# pcb.net
KiCad netlist of a schematic drawn in EasyEDA Pro
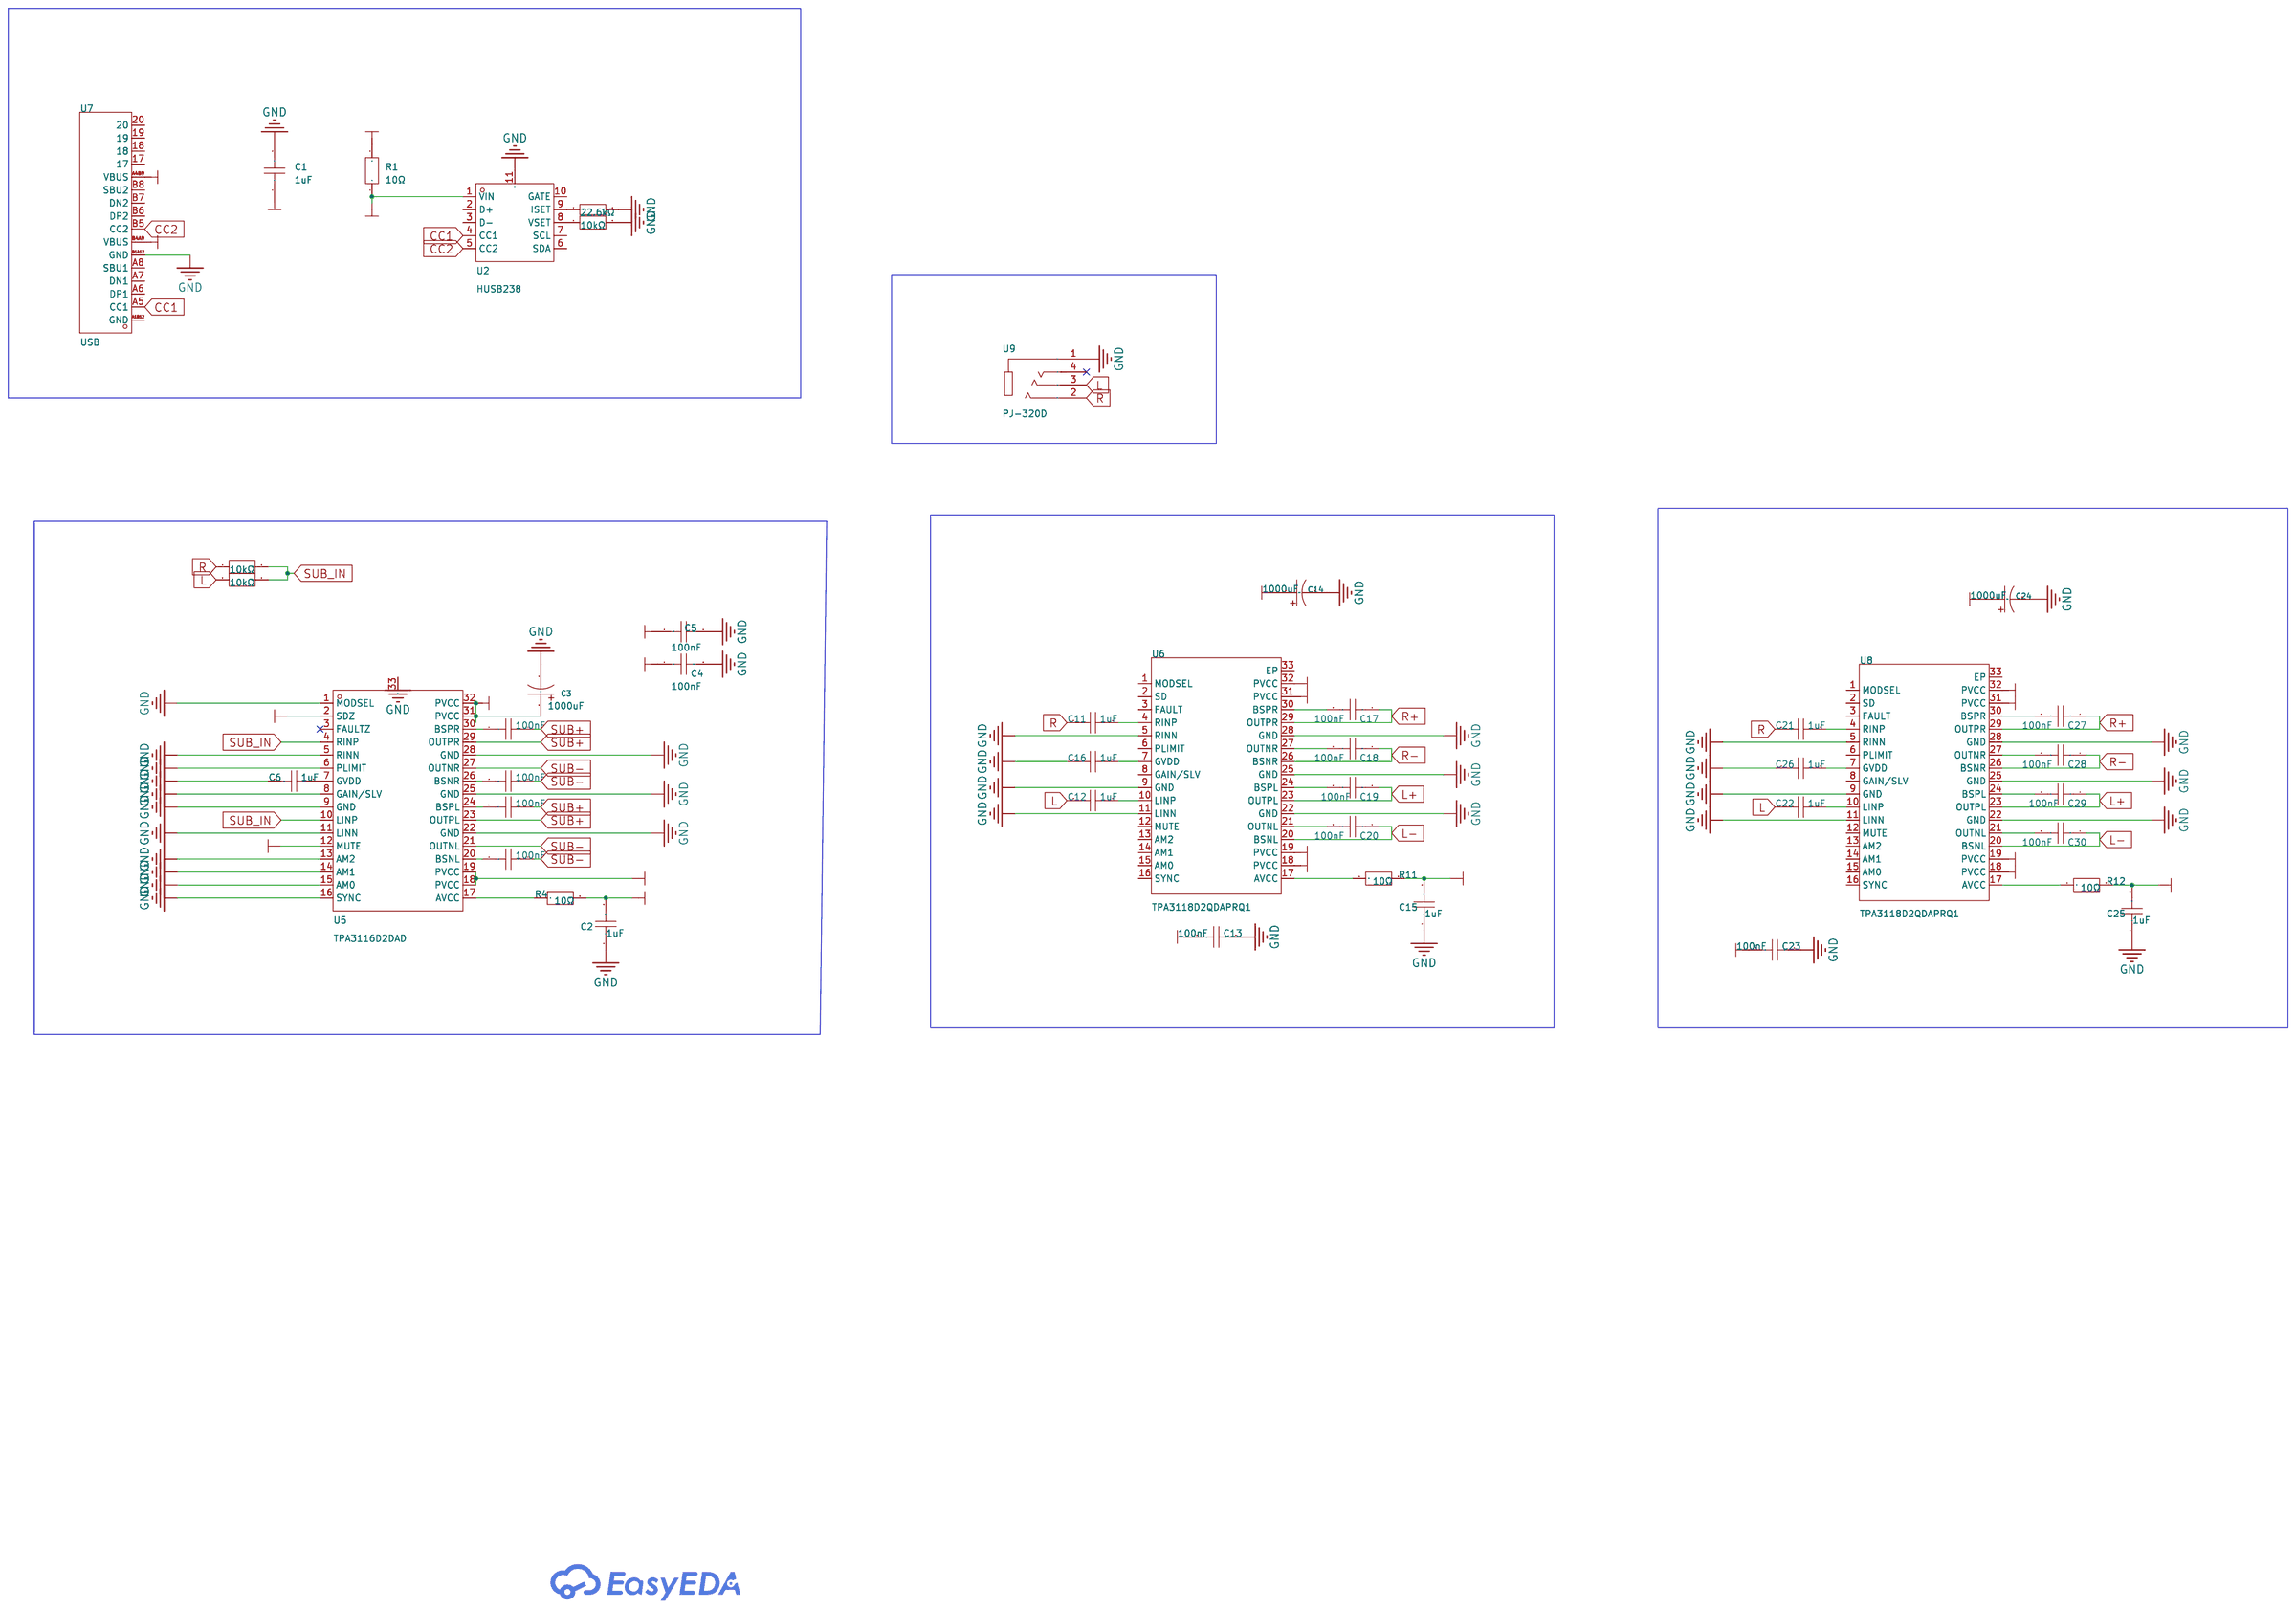
[diagram p0: schematic sheet]

(export (version "E")
  (design (tool "Eeschema 10.0.6"))
  (components
    (comp (ref "C1")
      (value "1uF")
      (footprint "easyedapro:C0805")
      (fields
        (field (name "Manufacturer Part") "LMK212BJ105KG-T")
        (field (name "Manufacturer") "TAIYO YUDEN(太诱)")
      )
      (libsource (lib "easyedapro") (part "LMK212BJ105KG-T"))
    )
    (comp (ref "C2")
      (value "1uF")
      (footprint "easyedapro:C0805")
      (fields
        (field (name "Manufacturer Part") "LMK212BJ105KG-T")
        (field (name "Manufacturer") "TAIYO YUDEN(太诱)")
      )
      (libsource (lib "easyedapro") (part "LMK212BJ105KG-T"))
    )
    (comp (ref "C3")
      (value "1000uF")
      (footprint "easyedapro:CAP-TH_BD12.5-P5.00-D0.6-FD")
      (fields
        (field (name "Manufacturer Part") "ECR1HBK102MLL125025")
        (field (name "Manufacturer") "Jianghai(南通江海)")
      )
      (libsource (lib "easyedapro") (part "ECR1HBK102MLL125025"))
    )
    (comp (ref "C4")
      (value "100nF")
      (footprint "easyedapro:C0603")
      (description "Capacitance:100nF Tolerance:±10% Tolerance:±10% Voltage Rating:50V Temperature Coefficient:X7R")
      (fields
        (field (name "Manufacturer Part") "CC0603KRX7R9BB104")
        (field (name "Manufacturer") "YAGEO(国巨)")
      )
      (libsource (lib "easyedapro") (part "CC0603KRX7R9BB104"))
    )
    (comp (ref "C5")
      (value "100nF")
      (footprint "easyedapro:C0603")
      (description "Capacitance:100nF Tolerance:±10% Tolerance:±10% Voltage Rating:50V Temperature Coefficient:X7R")
      (fields
        (field (name "Manufacturer Part") "CC0603KRX7R9BB104")
        (field (name "Manufacturer") "YAGEO(国巨)")
      )
      (libsource (lib "easyedapro") (part "CC0603KRX7R9BB104"))
    )
    (comp (ref "C6")
      (value "1uF")
      (footprint "easyedapro:C0805")
      (fields
        (field (name "Manufacturer Part") "LMK212BJ105KG-T")
        (field (name "Manufacturer") "TAIYO YUDEN(太诱)")
      )
      (libsource (lib "easyedapro") (part "LMK212BJ105KG-T"))
    )
    (comp (ref "C7")
      (value "100nF")
      (footprint "easyedapro:C0603")
      (description "Capacitance:100nF Tolerance:±10% Tolerance:±10% Voltage Rating:50V Temperature Coefficient:X7R")
      (fields
        (field (name "Manufacturer Part") "CC0603KRX7R9BB104")
        (field (name "Manufacturer") "YAGEO(国巨)")
      )
      (libsource (lib "easyedapro") (part "CC0603KRX7R9BB104"))
    )
    (comp (ref "C8")
      (value "100nF")
      (footprint "easyedapro:C0603")
      (description "Capacitance:100nF Tolerance:±10% Tolerance:±10% Voltage Rating:50V Temperature Coefficient:X7R")
      (fields
        (field (name "Manufacturer Part") "CC0603KRX7R9BB104")
        (field (name "Manufacturer") "YAGEO(国巨)")
      )
      (libsource (lib "easyedapro") (part "CC0603KRX7R9BB104"))
    )
    (comp (ref "C9")
      (value "100nF")
      (footprint "easyedapro:C0603")
      (description "Capacitance:100nF Tolerance:±10% Tolerance:±10% Voltage Rating:50V Temperature Coefficient:X7R")
      (fields
        (field (name "Manufacturer Part") "CC0603KRX7R9BB104")
        (field (name "Manufacturer") "YAGEO(国巨)")
      )
      (libsource (lib "easyedapro") (part "CC0603KRX7R9BB104"))
    )
    (comp (ref "C10")
      (value "100nF")
      (footprint "easyedapro:C0603")
      (description "Capacitance:100nF Tolerance:±10% Tolerance:±10% Voltage Rating:50V Temperature Coefficient:X7R")
      (fields
        (field (name "Manufacturer Part") "CC0603KRX7R9BB104")
        (field (name "Manufacturer") "YAGEO(国巨)")
      )
      (libsource (lib "easyedapro") (part "CC0603KRX7R9BB104"))
    )
    (comp (ref "C11")
      (value "1uF")
      (footprint "easyedapro:C0805")
      (fields
        (field (name "Manufacturer Part") "LMK212BJ105KG-T")
        (field (name "Manufacturer") "TAIYO YUDEN(太诱)")
      )
      (libsource (lib "easyedapro") (part "LMK212BJ105KG-T"))
    )
    (comp (ref "C12")
      (value "1uF")
      (footprint "easyedapro:C0805")
      (fields
        (field (name "Manufacturer Part") "LMK212BJ105KG-T")
        (field (name "Manufacturer") "TAIYO YUDEN(太诱)")
      )
      (libsource (lib "easyedapro") (part "LMK212BJ105KG-T"))
    )
    (comp (ref "C13")
      (value "100nF")
      (footprint "easyedapro:C0603")
      (description "Capacitance:100nF Tolerance:±10% Tolerance:±10% Voltage Rating:50V Temperature Coefficient:X7R")
      (fields
        (field (name "Manufacturer Part") "CC0603KRX7R9BB104")
        (field (name "Manufacturer") "YAGEO(国巨)")
      )
      (libsource (lib "easyedapro") (part "CC0603KRX7R9BB104"))
    )
    (comp (ref "C14")
      (value "1000uF")
      (footprint "easyedapro:CAP-TH_BD12.5-P5.00-D0.6-FD")
      (fields
        (field (name "Manufacturer Part") "ECR1HBK102MLL125025")
        (field (name "Manufacturer") "Jianghai(南通江海)")
      )
      (libsource (lib "easyedapro") (part "ECR1HBK102MLL125025"))
    )
    (comp (ref "C15")
      (value "1uF")
      (footprint "easyedapro:C0805")
      (fields
        (field (name "Manufacturer Part") "LMK212BJ105KG-T")
        (field (name "Manufacturer") "TAIYO YUDEN(太诱)")
      )
      (libsource (lib "easyedapro") (part "LMK212BJ105KG-T"))
    )
    (comp (ref "C16")
      (value "1uF")
      (footprint "easyedapro:C0805")
      (fields
        (field (name "Manufacturer Part") "LMK212BJ105KG-T")
        (field (name "Manufacturer") "TAIYO YUDEN(太诱)")
      )
      (libsource (lib "easyedapro") (part "LMK212BJ105KG-T"))
    )
    (comp (ref "C17")
      (value "100nF")
      (footprint "easyedapro:C0603")
      (description "Capacitance:100nF Tolerance:±10% Tolerance:±10% Voltage Rating:50V Temperature Coefficient:X7R")
      (fields
        (field (name "Manufacturer Part") "CC0603KRX7R9BB104")
        (field (name "Manufacturer") "YAGEO(国巨)")
      )
      (libsource (lib "easyedapro") (part "CC0603KRX7R9BB104"))
    )
    (comp (ref "C18")
      (value "100nF")
      (footprint "easyedapro:C0603")
      (description "Capacitance:100nF Tolerance:±10% Tolerance:±10% Voltage Rating:50V Temperature Coefficient:X7R")
      (fields
        (field (name "Manufacturer Part") "CC0603KRX7R9BB104")
        (field (name "Manufacturer") "YAGEO(国巨)")
      )
      (libsource (lib "easyedapro") (part "CC0603KRX7R9BB104"))
    )
    (comp (ref "C19")
      (value "100nF")
      (footprint "easyedapro:C0603")
      (description "Capacitance:100nF Tolerance:±10% Tolerance:±10% Voltage Rating:50V Temperature Coefficient:X7R")
      (fields
        (field (name "Manufacturer Part") "CC0603KRX7R9BB104")
        (field (name "Manufacturer") "YAGEO(国巨)")
      )
      (libsource (lib "easyedapro") (part "CC0603KRX7R9BB104"))
    )
    (comp (ref "C20")
      (value "100nF")
      (footprint "easyedapro:C0603")
      (description "Capacitance:100nF Tolerance:±10% Tolerance:±10% Voltage Rating:50V Temperature Coefficient:X7R")
      (fields
        (field (name "Manufacturer Part") "CC0603KRX7R9BB104")
        (field (name "Manufacturer") "YAGEO(国巨)")
      )
      (libsource (lib "easyedapro") (part "CC0603KRX7R9BB104"))
    )
    (comp (ref "C21")
      (value "1uF")
      (footprint "easyedapro:C0805")
      (fields
        (field (name "Manufacturer Part") "LMK212BJ105KG-T")
        (field (name "Manufacturer") "TAIYO YUDEN(太诱)")
      )
      (libsource (lib "easyedapro") (part "LMK212BJ105KG-T"))
    )
    (comp (ref "C22")
      (value "1uF")
      (footprint "easyedapro:C0805")
      (fields
        (field (name "Manufacturer Part") "LMK212BJ105KG-T")
        (field (name "Manufacturer") "TAIYO YUDEN(太诱)")
      )
      (libsource (lib "easyedapro") (part "LMK212BJ105KG-T"))
    )
    (comp (ref "C23")
      (value "100nF")
      (footprint "easyedapro:C0603")
      (description "Capacitance:100nF Tolerance:±10% Tolerance:±10% Voltage Rating:50V Temperature Coefficient:X7R")
      (fields
        (field (name "Manufacturer Part") "CC0603KRX7R9BB104")
        (field (name "Manufacturer") "YAGEO(国巨)")
      )
      (libsource (lib "easyedapro") (part "CC0603KRX7R9BB104"))
    )
    (comp (ref "C24")
      (value "1000uF")
      (footprint "easyedapro:CAP-TH_BD12.5-P5.00-D0.6-FD")
      (fields
        (field (name "Manufacturer Part") "ECR1HBK102MLL125025")
        (field (name "Manufacturer") "Jianghai(南通江海)")
      )
      (libsource (lib "easyedapro") (part "ECR1HBK102MLL125025"))
    )
    (comp (ref "C25")
      (value "1uF")
      (footprint "easyedapro:C0805")
      (fields
        (field (name "Manufacturer Part") "LMK212BJ105KG-T")
        (field (name "Manufacturer") "TAIYO YUDEN(太诱)")
      )
      (libsource (lib "easyedapro") (part "LMK212BJ105KG-T"))
    )
    (comp (ref "C26")
      (value "1uF")
      (footprint "easyedapro:C0805")
      (fields
        (field (name "Manufacturer Part") "LMK212BJ105KG-T")
        (field (name "Manufacturer") "TAIYO YUDEN(太诱)")
      )
      (libsource (lib "easyedapro") (part "LMK212BJ105KG-T"))
    )
    (comp (ref "C27")
      (value "100nF")
      (footprint "easyedapro:C0603")
      (description "Capacitance:100nF Tolerance:±10% Tolerance:±10% Voltage Rating:50V Temperature Coefficient:X7R")
      (fields
        (field (name "Manufacturer Part") "CC0603KRX7R9BB104")
        (field (name "Manufacturer") "YAGEO(国巨)")
      )
      (libsource (lib "easyedapro") (part "CC0603KRX7R9BB104"))
    )
    (comp (ref "C28")
      (value "100nF")
      (footprint "easyedapro:C0603")
      (description "Capacitance:100nF Tolerance:±10% Tolerance:±10% Voltage Rating:50V Temperature Coefficient:X7R")
      (fields
        (field (name "Manufacturer Part") "CC0603KRX7R9BB104")
        (field (name "Manufacturer") "YAGEO(国巨)")
      )
      (libsource (lib "easyedapro") (part "CC0603KRX7R9BB104"))
    )
    (comp (ref "C29")
      (value "100nF")
      (footprint "easyedapro:C0603")
      (description "Capacitance:100nF Tolerance:±10% Tolerance:±10% Voltage Rating:50V Temperature Coefficient:X7R")
      (fields
        (field (name "Manufacturer Part") "CC0603KRX7R9BB104")
        (field (name "Manufacturer") "YAGEO(国巨)")
      )
      (libsource (lib "easyedapro") (part "CC0603KRX7R9BB104"))
    )
    (comp (ref "C30")
      (value "100nF")
      (footprint "easyedapro:C0603")
      (description "Capacitance:100nF Tolerance:±10% Tolerance:±10% Voltage Rating:50V Temperature Coefficient:X7R")
      (fields
        (field (name "Manufacturer Part") "CC0603KRX7R9BB104")
        (field (name "Manufacturer") "YAGEO(国巨)")
      )
      (libsource (lib "easyedapro") (part "CC0603KRX7R9BB104"))
    )
    (comp (ref "R1")
      (value "10Ω")
      (footprint "easyedapro:R0805")
      (fields (field (name "Manufacturer Part") "MMV05F10R0E") (field (name "Manufacturer") "Ohmite"))
      (libsource (lib "easyedapro") (part "MMV05F10R0E"))
    )
    (comp (ref "R2")
      (value "10kΩ")
      (footprint "easyedapro:R0805")
      (description "Resistance:10kΩ Tolerance:±1% Tolerance:±1%")
      (fields (field (name "Manufacturer Part") "RK73H2ATTE1002F") (field (name "Manufacturer") "KOA"))
      (libsource (lib "easyedapro") (part "RK73H2ATTE1002F"))
    )
    (comp (ref "R3")
      (value "22.6kΩ")
      (footprint "easyedapro:R0805")
      (fields (field (name "Manufacturer Part") "0805W8F2262T5E"))
      (libsource (lib "easyedapro") (part "0805W8F2262T5E"))
    )
    (comp (ref "R4")
      (value "10Ω")
      (footprint "easyedapro:R0805")
      (fields (field (name "Manufacturer Part") "MMV05F10R0E") (field (name "Manufacturer") "Ohmite"))
      (libsource (lib "easyedapro") (part "MMV05F10R0E"))
    )
    (comp (ref "R9")
      (value "10kΩ")
      (footprint "easyedapro:R0805")
      (description "Resistance:10kΩ Tolerance:±1% Tolerance:±1%")
      (fields (field (name "Manufacturer Part") "RK73H2ATTE1002F") (field (name "Manufacturer") "KOA"))
      (libsource (lib "easyedapro") (part "RK73H2ATTE1002F"))
    )
    (comp (ref "R10")
      (value "10kΩ")
      (footprint "easyedapro:R0805")
      (description "Resistance:10kΩ Tolerance:±1% Tolerance:±1%")
      (fields (field (name "Manufacturer Part") "RK73H2ATTE1002F") (field (name "Manufacturer") "KOA"))
      (libsource (lib "easyedapro") (part "RK73H2ATTE1002F"))
    )
    (comp (ref "R11")
      (value "10Ω")
      (footprint "easyedapro:R0805")
      (fields (field (name "Manufacturer Part") "MMV05F10R0E") (field (name "Manufacturer") "Ohmite"))
      (libsource (lib "easyedapro") (part "MMV05F10R0E"))
    )
    (comp (ref "R12")
      (value "10Ω")
      (footprint "easyedapro:R0805")
      (fields (field (name "Manufacturer Part") "MMV05F10R0E") (field (name "Manufacturer") "Ohmite"))
      (libsource (lib "easyedapro") (part "MMV05F10R0E"))
    )
    (comp (ref "U2")
      (value "HUSB238")
      (footprint "easyedapro:TDFN-10_L3.0-W3.0-P0.50-TL-EP")
      (libsource (lib "easyedapro") (part "HUSB238"))
    )
    (comp (ref "U5")
      (value "TPA3116D2DAD")
      (footprint "easyedapro:HTSSOP-32_L11.0-W6.1-P0.65-LS8.1-BL")
      (fields (field (name "Manufacturer") "TI(德州仪器)"))
      (libsource (lib "easyedapro") (part "TPA3116D2DAD_C2865736"))
    )
    (comp (ref "U6")
      (value "TPA3118D2QDAPRQ1")
      (footprint "easyedapro:HTSSOP-32_L11.0-W6.1-P0.65-LS8.1-EP3.5_TPA3118D2QDAPRQ1")
      (fields (field (name "Manufacturer") "TI(德州仪器)"))
      (libsource (lib "easyedapro") (part "TPA3118D2QDAPRQ1"))
    )
    (comp (ref "U7")
      (value "USB")
      (footprint "easyedapro:USB-SMD_TYPE-C16PIN-1")
      (libsource (lib "easyedapro") (part "USB_C_RECEPTACLE_HRO_TYPE-C-31-M-12"))
    )
    (comp (ref "U8")
      (value "TPA3118D2QDAPRQ1")
      (footprint "easyedapro:HTSSOP-32_L11.0-W6.1-P0.65-LS8.1-EP3.5_TPA3118D2QDAPRQ1")
      (fields (field (name "Manufacturer") "TI(德州仪器)"))
      (libsource (lib "easyedapro") (part "TPA3118D2QDAPRQ1"))
    )
    (comp (ref "U9")
      (value "PJ-320D")
      (footprint "easyedapro:AUDIO-SMD_HANELECTRICITY_PJ-320D")
      (fields (field (name "Manufacturer") "HanElectricity(瀚源)"))
      (libsource (lib "easyedapro") (part "PJ-320D_C22459515"))
    )
  )
  (nets
    (net (code "1") (name "+12V") (class "Default")
      (node (ref "C13") (pin "2") (pinfunction "2_2") (pintype "unspecified"))
      (node (ref "C14") (pin "1") (pinfunction "1_1") (pintype "input"))
      (node (ref "C15") (pin "2") (pinfunction "2_2") (pintype "unspecified"))
      (node (ref "C2") (pin "2") (pinfunction "2_2") (pintype "unspecified"))
      (node (ref "C23") (pin "2") (pinfunction "2_2") (pintype "unspecified"))
      (node (ref "C24") (pin "1") (pinfunction "1_1") (pintype "input"))
      (node (ref "C25") (pin "2") (pinfunction "2_2") (pintype "unspecified"))
      (node (ref "C3") (pin "1") (pinfunction "1_1") (pintype "input"))
      (node (ref "C4") (pin "2") (pinfunction "2_2") (pintype "unspecified"))
      (node (ref "C5") (pin "2") (pinfunction "2_2") (pintype "unspecified"))
      (node (ref "R1") (pin "2") (pinfunction "2_2") (pintype "unspecified"))
      (node (ref "R11") (pin "2") (pinfunction "2_2") (pintype "unspecified"))
      (node (ref "R12") (pin "2") (pinfunction "2_2") (pintype "unspecified"))
      (node (ref "R4") (pin "2") (pinfunction "2_2") (pintype "unspecified"))
      (node (ref "U5") (pin "12") (pinfunction "MUTE_12") (pintype "unspecified"))
      (node (ref "U5") (pin "18") (pinfunction "PVCC_18") (pintype "unspecified"))
      (node (ref "U5") (pin "19") (pinfunction "PVCC_19") (pintype "unspecified"))
      (node (ref "U5") (pin "2") (pinfunction "SDZ_2") (pintype "unspecified"))
      (node (ref "U5") (pin "31") (pinfunction "PVCC_31") (pintype "unspecified"))
      (node (ref "U5") (pin "32") (pinfunction "PVCC_32") (pintype "unspecified"))
      (node (ref "U6") (pin "18") (pinfunction "PVCC_18") (pintype "unspecified"))
      (node (ref "U6") (pin "19") (pinfunction "PVCC_19") (pintype "unspecified"))
      (node (ref "U6") (pin "31") (pinfunction "PVCC_31") (pintype "unspecified"))
      (node (ref "U6") (pin "32") (pinfunction "PVCC_32") (pintype "unspecified"))
      (node (ref "U8") (pin "18") (pinfunction "PVCC_18") (pintype "unspecified"))
      (node (ref "U8") (pin "19") (pinfunction "PVCC_19") (pintype "unspecified"))
      (node (ref "U8") (pin "31") (pinfunction "PVCC_31") (pintype "unspecified"))
      (node (ref "U8") (pin "32") (pinfunction "PVCC_32") (pintype "unspecified"))
    )
    (net (code "2") (name "CC1") (class "Default")
      (node (ref "U2") (pin "4") (pinfunction "CC1_4") (pintype "unspecified"))
      (node (ref "U7") (pin "A5") (pinfunction "CC1_A5") (pintype "unspecified"))
    )
    (net (code "3") (name "CC2") (class "Default")
      (node (ref "U2") (pin "5") (pinfunction "CC2_5") (pintype "unspecified"))
      (node (ref "U7") (pin "B5") (pinfunction "CC2_B5") (pintype "unspecified"))
    )
    (net (code "4") (name "GND") (class "Default")
      (node (ref "C1") (pin "2") (pinfunction "2_2") (pintype "unspecified"))
      (node (ref "C13") (pin "1") (pinfunction "1_1") (pintype "unspecified"))
      (node (ref "C14") (pin "2") (pinfunction "2_2") (pintype "input"))
      (node (ref "C15") (pin "1") (pinfunction "1_1") (pintype "unspecified"))
      (node (ref "C16") (pin "2") (pinfunction "2_2") (pintype "unspecified"))
      (node (ref "C2") (pin "1") (pinfunction "1_1") (pintype "unspecified"))
      (node (ref "C23") (pin "1") (pinfunction "1_1") (pintype "unspecified"))
      (node (ref "C24") (pin "2") (pinfunction "2_2") (pintype "input"))
      (node (ref "C25") (pin "1") (pinfunction "1_1") (pintype "unspecified"))
      (node (ref "C26") (pin "2") (pinfunction "2_2") (pintype "unspecified"))
      (node (ref "C3") (pin "2") (pinfunction "2_2") (pintype "input"))
      (node (ref "C4") (pin "1") (pinfunction "1_1") (pintype "unspecified"))
      (node (ref "C5") (pin "1") (pinfunction "1_1") (pintype "unspecified"))
      (node (ref "C6") (pin "2") (pinfunction "2_2") (pintype "unspecified"))
      (node (ref "R2") (pin "2") (pinfunction "2_2") (pintype "unspecified"))
      (node (ref "R3") (pin "2") (pinfunction "2_2") (pintype "input"))
      (node (ref "U2") (pin "11") (pinfunction "GND_11") (pintype "unspecified"))
      (node (ref "U5") (pin "1") (pinfunction "MODSEL_1") (pintype "unspecified"))
      (node (ref "U5") (pin "11") (pinfunction "LINN_11") (pintype "unspecified"))
      (node (ref "U5") (pin "13") (pinfunction "AM2_13") (pintype "unspecified"))
      (node (ref "U5") (pin "14") (pinfunction "AM1_14") (pintype "unspecified"))
      (node (ref "U5") (pin "15") (pinfunction "AM0_15") (pintype "unspecified"))
      (node (ref "U5") (pin "16") (pinfunction "SYNC_16") (pintype "unspecified"))
      (node (ref "U5") (pin "22") (pinfunction "GND_22") (pintype "unspecified"))
      (node (ref "U5") (pin "25") (pinfunction "GND_25") (pintype "unspecified"))
      (node (ref "U5") (pin "28") (pinfunction "GND_28") (pintype "unspecified"))
      (node (ref "U5") (pin "33") (pinfunction "PAD_33") (pintype "unspecified"))
      (node (ref "U5") (pin "5") (pinfunction "RINN_5") (pintype "unspecified"))
      (node (ref "U5") (pin "6") (pinfunction "PLIMIT_6") (pintype "unspecified"))
      (node (ref "U5") (pin "8") (pinfunction "GAIN/SLV_8") (pintype "unspecified"))
      (node (ref "U5") (pin "9") (pinfunction "GND_9") (pintype "unspecified"))
      (node (ref "U6") (pin "11") (pinfunction "LINN_11") (pintype "unspecified"))
      (node (ref "U6") (pin "22") (pinfunction "GND_22") (pintype "unspecified"))
      (node (ref "U6") (pin "25") (pinfunction "GND_25") (pintype "unspecified"))
      (node (ref "U6") (pin "28") (pinfunction "GND_28") (pintype "unspecified"))
      (node (ref "U6") (pin "5") (pinfunction "RINN_5") (pintype "unspecified"))
      (node (ref "U6") (pin "9") (pinfunction "GND_9") (pintype "unspecified"))
      (node (ref "U7") (pin "B1A12") (pinfunction "GND_B1A12") (pintype "unspecified"))
      (node (ref "U8") (pin "11") (pinfunction "LINN_11") (pintype "unspecified"))
      (node (ref "U8") (pin "22") (pinfunction "GND_22") (pintype "unspecified"))
      (node (ref "U8") (pin "25") (pinfunction "GND_25") (pintype "unspecified"))
      (node (ref "U8") (pin "28") (pinfunction "GND_28") (pintype "unspecified"))
      (node (ref "U8") (pin "5") (pinfunction "RINN_5") (pintype "unspecified"))
      (node (ref "U8") (pin "9") (pinfunction "GND_9") (pintype "unspecified"))
      (node (ref "U9") (pin "1") (pinfunction "1_1") (pintype "unspecified"))
    )
    (net (code "5") (name "L") (class "Default")
      (node (ref "C12") (pin "2") (pinfunction "2_2") (pintype "unspecified"))
      (node (ref "C22") (pin "2") (pinfunction "2_2") (pintype "unspecified"))
      (node (ref "R10") (pin "1") (pinfunction "1_1") (pintype "unspecified"))
      (node (ref "U9") (pin "3") (pinfunction "3_3") (pintype "unspecified"))
    )
    (net (code "6") (name "L+") (class "Default")
      (node (ref "C19") (pin "1") (pinfunction "1_1") (pintype "unspecified"))
      (node (ref "C29") (pin "1") (pinfunction "1_1") (pintype "unspecified"))
      (node (ref "U6") (pin "23") (pinfunction "OUTPL_23") (pintype "unspecified"))
      (node (ref "U8") (pin "23") (pinfunction "OUTPL_23") (pintype "unspecified"))
    )
    (net (code "7") (name "L-") (class "Default")
      (node (ref "C20") (pin "1") (pinfunction "1_1") (pintype "unspecified"))
      (node (ref "C30") (pin "1") (pinfunction "1_1") (pintype "unspecified"))
      (node (ref "U6") (pin "20") (pinfunction "BSNL_20") (pintype "unspecified"))
      (node (ref "U8") (pin "20") (pinfunction "BSNL_20") (pintype "unspecified"))
    )
    (net (code "8") (name "Net-(U2-ISET)") (class "Default")
      (node (ref "R3") (pin "1") (pinfunction "1_1") (pintype "input"))
      (node (ref "U2") (pin "9") (pinfunction "ISET_9") (pintype "unspecified"))
    )
    (net (code "9") (name "Net-(U2-VSET)") (class "Default")
      (node (ref "R2") (pin "1") (pinfunction "1_1") (pintype "unspecified"))
      (node (ref "U2") (pin "8") (pinfunction "VSET_8") (pintype "unspecified"))
    )
    (net (code "10") (name "Net-(U5-AVCC)") (class "Default")
      (node (ref "R4") (pin "1") (pinfunction "1_1") (pintype "unspecified"))
      (node (ref "U5") (pin "17") (pinfunction "AVCC_17") (pintype "unspecified"))
    )
    (net (code "11") (name "Net-(U5-BSNL)") (class "Default")
      (node (ref "C8") (pin "2") (pinfunction "2_2") (pintype "unspecified"))
      (node (ref "U5") (pin "20") (pinfunction "BSNL_20") (pintype "unspecified"))
    )
    (net (code "12") (name "Net-(U5-BSNR)") (class "Default")
      (node (ref "C10") (pin "2") (pinfunction "2_2") (pintype "unspecified"))
      (node (ref "U5") (pin "26") (pinfunction "BSNR_26") (pintype "unspecified"))
    )
    (net (code "13") (name "Net-(U5-BSPL)") (class "Default")
      (node (ref "C7") (pin "2") (pinfunction "2_2") (pintype "unspecified"))
      (node (ref "U5") (pin "24") (pinfunction "BSPL_24") (pintype "unspecified"))
    )
    (net (code "14") (name "Net-(U5-BSPR)") (class "Default")
      (node (ref "C9") (pin "2") (pinfunction "2_2") (pintype "unspecified"))
      (node (ref "U5") (pin "30") (pinfunction "BSPR_30") (pintype "unspecified"))
    )
    (net (code "15") (name "Net-(U5-GVDD)") (class "Default")
      (node (ref "C6") (pin "1") (pinfunction "1_1") (pintype "unspecified"))
      (node (ref "U5") (pin "7") (pinfunction "GVDD_7") (pintype "unspecified"))
    )
    (net (code "16") (name "Net-(U6-AVCC)") (class "Default")
      (node (ref "R11") (pin "1") (pinfunction "1_1") (pintype "unspecified"))
      (node (ref "U6") (pin "17") (pinfunction "AVCC_17") (pintype "unspecified"))
    )
    (net (code "17") (name "Net-(U6-BSPL)") (class "Default")
      (node (ref "C19") (pin "2") (pinfunction "2_2") (pintype "unspecified"))
      (node (ref "U6") (pin "24") (pinfunction "BSPL_24") (pintype "unspecified"))
    )
    (net (code "18") (name "Net-(U6-BSPR)") (class "Default")
      (node (ref "C17") (pin "2") (pinfunction "2_2") (pintype "unspecified"))
      (node (ref "U6") (pin "30") (pinfunction "BSPR_30") (pintype "unspecified"))
    )
    (net (code "19") (name "Net-(U6-GVDD)") (class "Default")
      (node (ref "C16") (pin "1") (pinfunction "1_1") (pintype "unspecified"))
      (node (ref "U6") (pin "7") (pinfunction "GVDD_7") (pintype "unspecified"))
    )
    (net (code "20") (name "Net-(U6-LINP)") (class "Default")
      (node (ref "C12") (pin "1") (pinfunction "1_1") (pintype "unspecified"))
      (node (ref "U6") (pin "10") (pinfunction "LINP_10") (pintype "unspecified"))
    )
    (net (code "21") (name "Net-(U6-OUTNL)") (class "Default")
      (node (ref "C20") (pin "2") (pinfunction "2_2") (pintype "unspecified"))
      (node (ref "U6") (pin "21") (pinfunction "OUTNL_21") (pintype "unspecified"))
    )
    (net (code "22") (name "Net-(U6-OUTNR)") (class "Default")
      (node (ref "C18") (pin "2") (pinfunction "2_2") (pintype "unspecified"))
      (node (ref "U6") (pin "27") (pinfunction "OUTNR_27") (pintype "unspecified"))
    )
    (net (code "23") (name "Net-(U6-RINP)") (class "Default")
      (node (ref "C11") (pin "1") (pinfunction "1_1") (pintype "unspecified"))
      (node (ref "U6") (pin "4") (pinfunction "RINP_4") (pintype "unspecified"))
    )
    (net (code "24") (name "Net-(U8-AVCC)") (class "Default")
      (node (ref "R12") (pin "1") (pinfunction "1_1") (pintype "unspecified"))
      (node (ref "U8") (pin "17") (pinfunction "AVCC_17") (pintype "unspecified"))
    )
    (net (code "25") (name "Net-(U8-BSPL)") (class "Default")
      (node (ref "C29") (pin "2") (pinfunction "2_2") (pintype "unspecified"))
      (node (ref "U8") (pin "24") (pinfunction "BSPL_24") (pintype "unspecified"))
    )
    (net (code "26") (name "Net-(U8-BSPR)") (class "Default")
      (node (ref "C27") (pin "2") (pinfunction "2_2") (pintype "unspecified"))
      (node (ref "U8") (pin "30") (pinfunction "BSPR_30") (pintype "unspecified"))
    )
    (net (code "27") (name "Net-(U8-GVDD)") (class "Default")
      (node (ref "C26") (pin "1") (pinfunction "1_1") (pintype "unspecified"))
      (node (ref "U8") (pin "7") (pinfunction "GVDD_7") (pintype "unspecified"))
    )
    (net (code "28") (name "Net-(U8-LINP)") (class "Default")
      (node (ref "C22") (pin "1") (pinfunction "1_1") (pintype "unspecified"))
      (node (ref "U8") (pin "10") (pinfunction "LINP_10") (pintype "unspecified"))
    )
    (net (code "29") (name "Net-(U8-OUTNL)") (class "Default")
      (node (ref "C30") (pin "2") (pinfunction "2_2") (pintype "unspecified"))
      (node (ref "U8") (pin "21") (pinfunction "OUTNL_21") (pintype "unspecified"))
    )
    (net (code "30") (name "Net-(U8-OUTNR)") (class "Default")
      (node (ref "C28") (pin "2") (pinfunction "2_2") (pintype "unspecified"))
      (node (ref "U8") (pin "27") (pinfunction "OUTNR_27") (pintype "unspecified"))
    )
    (net (code "31") (name "Net-(U8-RINP)") (class "Default")
      (node (ref "C21") (pin "1") (pinfunction "1_1") (pintype "unspecified"))
      (node (ref "U8") (pin "4") (pinfunction "RINP_4") (pintype "unspecified"))
    )
    (net (code "32") (name "R") (class "Default")
      (node (ref "C11") (pin "2") (pinfunction "2_2") (pintype "unspecified"))
      (node (ref "C21") (pin "2") (pinfunction "2_2") (pintype "unspecified"))
      (node (ref "R9") (pin "1") (pinfunction "1_1") (pintype "unspecified"))
      (node (ref "U9") (pin "2") (pinfunction "2_2") (pintype "unspecified"))
    )
    (net (code "33") (name "R+") (class "Default")
      (node (ref "C17") (pin "1") (pinfunction "1_1") (pintype "unspecified"))
      (node (ref "C27") (pin "1") (pinfunction "1_1") (pintype "unspecified"))
      (node (ref "U6") (pin "29") (pinfunction "OUTPR_29") (pintype "unspecified"))
      (node (ref "U8") (pin "29") (pinfunction "OUTPR_29") (pintype "unspecified"))
    )
    (net (code "34") (name "R-") (class "Default")
      (node (ref "C18") (pin "1") (pinfunction "1_1") (pintype "unspecified"))
      (node (ref "C28") (pin "1") (pinfunction "1_1") (pintype "unspecified"))
      (node (ref "U6") (pin "26") (pinfunction "BSNR_26") (pintype "unspecified"))
      (node (ref "U8") (pin "26") (pinfunction "BSNR_26") (pintype "unspecified"))
    )
    (net (code "35") (name "SUB+") (class "Default")
      (node (ref "C7") (pin "1") (pinfunction "1_1") (pintype "unspecified"))
      (node (ref "C9") (pin "1") (pinfunction "1_1") (pintype "unspecified"))
      (node (ref "U5") (pin "23") (pinfunction "OUTPL_23") (pintype "unspecified"))
      (node (ref "U5") (pin "29") (pinfunction "OUTPR_29") (pintype "unspecified"))
    )
    (net (code "36") (name "SUB-") (class "Default")
      (node (ref "C10") (pin "1") (pinfunction "1_1") (pintype "unspecified"))
      (node (ref "C8") (pin "1") (pinfunction "1_1") (pintype "unspecified"))
      (node (ref "U5") (pin "21") (pinfunction "OUTNL_21") (pintype "unspecified"))
      (node (ref "U5") (pin "27") (pinfunction "OUTNR_27") (pintype "unspecified"))
    )
    (net (code "37") (name "SUB_IN") (class "Default")
      (node (ref "R10") (pin "2") (pinfunction "2_2") (pintype "unspecified"))
      (node (ref "R9") (pin "2") (pinfunction "2_2") (pintype "unspecified"))
      (node (ref "U5") (pin "10") (pinfunction "LINP_10") (pintype "unspecified"))
      (node (ref "U5") (pin "4") (pinfunction "RINP_4") (pintype "unspecified"))
    )
    (net (code "38") (name "VBUS") (class "Default")
      (node (ref "C1") (pin "1") (pinfunction "1_1") (pintype "unspecified"))
      (node (ref "R1") (pin "1") (pinfunction "1_1") (pintype "unspecified"))
      (node (ref "U2") (pin "1") (pinfunction "VIN_1") (pintype "unspecified"))
      (node (ref "U7") (pin "A4B9") (pinfunction "VBUS_A4B9") (pintype "unspecified"))
      (node (ref "U7") (pin "B4A9") (pinfunction "VBUS_B4A9") (pintype "unspecified"))
    )
    (net (code "39") (name "unconnected-(U2-D+-Pad2)") (class "Default")
      (node (ref "U2") (pin "2") (pinfunction "D+_2") (pintype "unspecified"))
    )
    (net (code "40") (name "unconnected-(U2-D--Pad3)") (class "Default")
      (node (ref "U2") (pin "3") (pinfunction "D-_3") (pintype "unspecified"))
    )
    (net (code "41") (name "unconnected-(U2-GATE-Pad10)") (class "Default")
      (node (ref "U2") (pin "10") (pinfunction "GATE_10") (pintype "unspecified"))
    )
    (net (code "42") (name "unconnected-(U2-SCL-Pad7)") (class "Default")
      (node (ref "U2") (pin "7") (pinfunction "SCL_7") (pintype "unspecified"))
    )
    (net (code "43") (name "unconnected-(U2-SDA-Pad6)") (class "Default")
      (node (ref "U2") (pin "6") (pinfunction "SDA_6") (pintype "unspecified"))
    )
    (net (code "44") (name "unconnected-(U5-FAULTZ-Pad3)") (class "Default")
      (node (ref "U5") (pin "3") (pinfunction "FAULTZ_3") (pintype "unspecified+no_connect"))
    )
    (net (code "45") (name "unconnected-(U6-AM0-Pad15)") (class "Default")
      (node (ref "U6") (pin "15") (pinfunction "AM0_15") (pintype "unspecified"))
    )
    (net (code "46") (name "unconnected-(U6-AM1-Pad14)") (class "Default")
      (node (ref "U6") (pin "14") (pinfunction "AM1_14") (pintype "unspecified"))
    )
    (net (code "47") (name "unconnected-(U6-AM2-Pad13)") (class "Default")
      (node (ref "U6") (pin "13") (pinfunction "AM2_13") (pintype "unspecified"))
    )
    (net (code "48") (name "unconnected-(U6-EP-Pad33)") (class "Default")
      (node (ref "U6") (pin "33") (pinfunction "EP_33") (pintype "unspecified"))
    )
    (net (code "49") (name "unconnected-(U6-FAULT-Pad3)") (class "Default")
      (node (ref "U6") (pin "3") (pinfunction "FAULT_3") (pintype "unspecified"))
    )
    (net (code "50") (name "unconnected-(U6-GAIN{slash}SLV-Pad8)") (class "Default")
      (node (ref "U6") (pin "8") (pinfunction "GAIN/SLV_8") (pintype "unspecified"))
    )
    (net (code "51") (name "unconnected-(U6-MODSEL-Pad1)") (class "Default")
      (node (ref "U6") (pin "1") (pinfunction "MODSEL_1") (pintype "unspecified"))
    )
    (net (code "52") (name "unconnected-(U6-MUTE-Pad12)") (class "Default")
      (node (ref "U6") (pin "12") (pinfunction "MUTE_12") (pintype "unspecified"))
    )
    (net (code "53") (name "unconnected-(U6-PLIMIT-Pad6)") (class "Default")
      (node (ref "U6") (pin "6") (pinfunction "PLIMIT_6") (pintype "unspecified"))
    )
    (net (code "54") (name "unconnected-(U6-SD-Pad2)") (class "Default")
      (node (ref "U6") (pin "2") (pinfunction "SD_2") (pintype "unspecified"))
    )
    (net (code "55") (name "unconnected-(U6-SYNC-Pad16)") (class "Default")
      (node (ref "U6") (pin "16") (pinfunction "SYNC_16") (pintype "unspecified"))
    )
    (net (code "56") (name "unconnected-(U7-DN1-PadA7)") (class "Default")
      (node (ref "U7") (pin "A7") (pinfunction "DN1_A7") (pintype "unspecified"))
    )
    (net (code "57") (name "unconnected-(U7-DN2-PadB7)") (class "Default")
      (node (ref "U7") (pin "B7") (pinfunction "DN2_B7") (pintype "unspecified"))
    )
    (net (code "58") (name "unconnected-(U7-DP1-PadA6)") (class "Default")
      (node (ref "U7") (pin "A6") (pinfunction "DP1_A6") (pintype "unspecified"))
    )
    (net (code "59") (name "unconnected-(U7-DP2-PadB6)") (class "Default")
      (node (ref "U7") (pin "B6") (pinfunction "DP2_B6") (pintype "unspecified"))
    )
    (net (code "60") (name "unconnected-(U7-GND-PadA1B12)") (class "Default")
      (node (ref "U7") (pin "A1B12") (pinfunction "GND_A1B12") (pintype "unspecified"))
    )
    (net (code "61") (name "unconnected-(U7-Pad17)") (class "Default")
      (node (ref "U7") (pin "17") (pinfunction "17_17") (pintype "unspecified"))
    )
    (net (code "62") (name "unconnected-(U7-Pad18)") (class "Default")
      (node (ref "U7") (pin "18") (pinfunction "18_18") (pintype "unspecified"))
    )
    (net (code "63") (name "unconnected-(U7-Pad19)") (class "Default")
      (node (ref "U7") (pin "19") (pinfunction "19_19") (pintype "unspecified"))
    )
    (net (code "64") (name "unconnected-(U7-Pad20)") (class "Default")
      (node (ref "U7") (pin "20") (pinfunction "20_20") (pintype "unspecified"))
    )
    (net (code "65") (name "unconnected-(U7-SBU1-PadA8)") (class "Default")
      (node (ref "U7") (pin "A8") (pinfunction "SBU1_A8") (pintype "unspecified"))
    )
    (net (code "66") (name "unconnected-(U7-SBU2-PadB8)") (class "Default")
      (node (ref "U7") (pin "B8") (pinfunction "SBU2_B8") (pintype "unspecified"))
    )
    (net (code "67") (name "unconnected-(U8-AM0-Pad15)") (class "Default")
      (node (ref "U8") (pin "15") (pinfunction "AM0_15") (pintype "unspecified"))
    )
    (net (code "68") (name "unconnected-(U8-AM1-Pad14)") (class "Default")
      (node (ref "U8") (pin "14") (pinfunction "AM1_14") (pintype "unspecified"))
    )
    (net (code "69") (name "unconnected-(U8-AM2-Pad13)") (class "Default")
      (node (ref "U8") (pin "13") (pinfunction "AM2_13") (pintype "unspecified"))
    )
    (net (code "70") (name "unconnected-(U8-EP-Pad33)") (class "Default")
      (node (ref "U8") (pin "33") (pinfunction "EP_33") (pintype "unspecified"))
    )
    (net (code "71") (name "unconnected-(U8-FAULT-Pad3)") (class "Default")
      (node (ref "U8") (pin "3") (pinfunction "FAULT_3") (pintype "unspecified"))
    )
    (net (code "72") (name "unconnected-(U8-GAIN{slash}SLV-Pad8)") (class "Default")
      (node (ref "U8") (pin "8") (pinfunction "GAIN/SLV_8") (pintype "unspecified"))
    )
    (net (code "73") (name "unconnected-(U8-MODSEL-Pad1)") (class "Default")
      (node (ref "U8") (pin "1") (pinfunction "MODSEL_1") (pintype "unspecified"))
    )
    (net (code "74") (name "unconnected-(U8-MUTE-Pad12)") (class "Default")
      (node (ref "U8") (pin "12") (pinfunction "MUTE_12") (pintype "unspecified"))
    )
    (net (code "75") (name "unconnected-(U8-PLIMIT-Pad6)") (class "Default")
      (node (ref "U8") (pin "6") (pinfunction "PLIMIT_6") (pintype "unspecified"))
    )
    (net (code "76") (name "unconnected-(U8-SD-Pad2)") (class "Default")
      (node (ref "U8") (pin "2") (pinfunction "SD_2") (pintype "unspecified"))
    )
    (net (code "77") (name "unconnected-(U8-SYNC-Pad16)") (class "Default")
      (node (ref "U8") (pin "16") (pinfunction "SYNC_16") (pintype "unspecified"))
    )
    (net (code "78") (name "unconnected-(U9-Pad4)") (class "Default")
      (node (ref "U9") (pin "4") (pinfunction "4_4") (pintype "unspecified+no_connect"))
    )
  )
)
